# ELED03.net
KiCad netlist of a schematic drawn in EAGLE
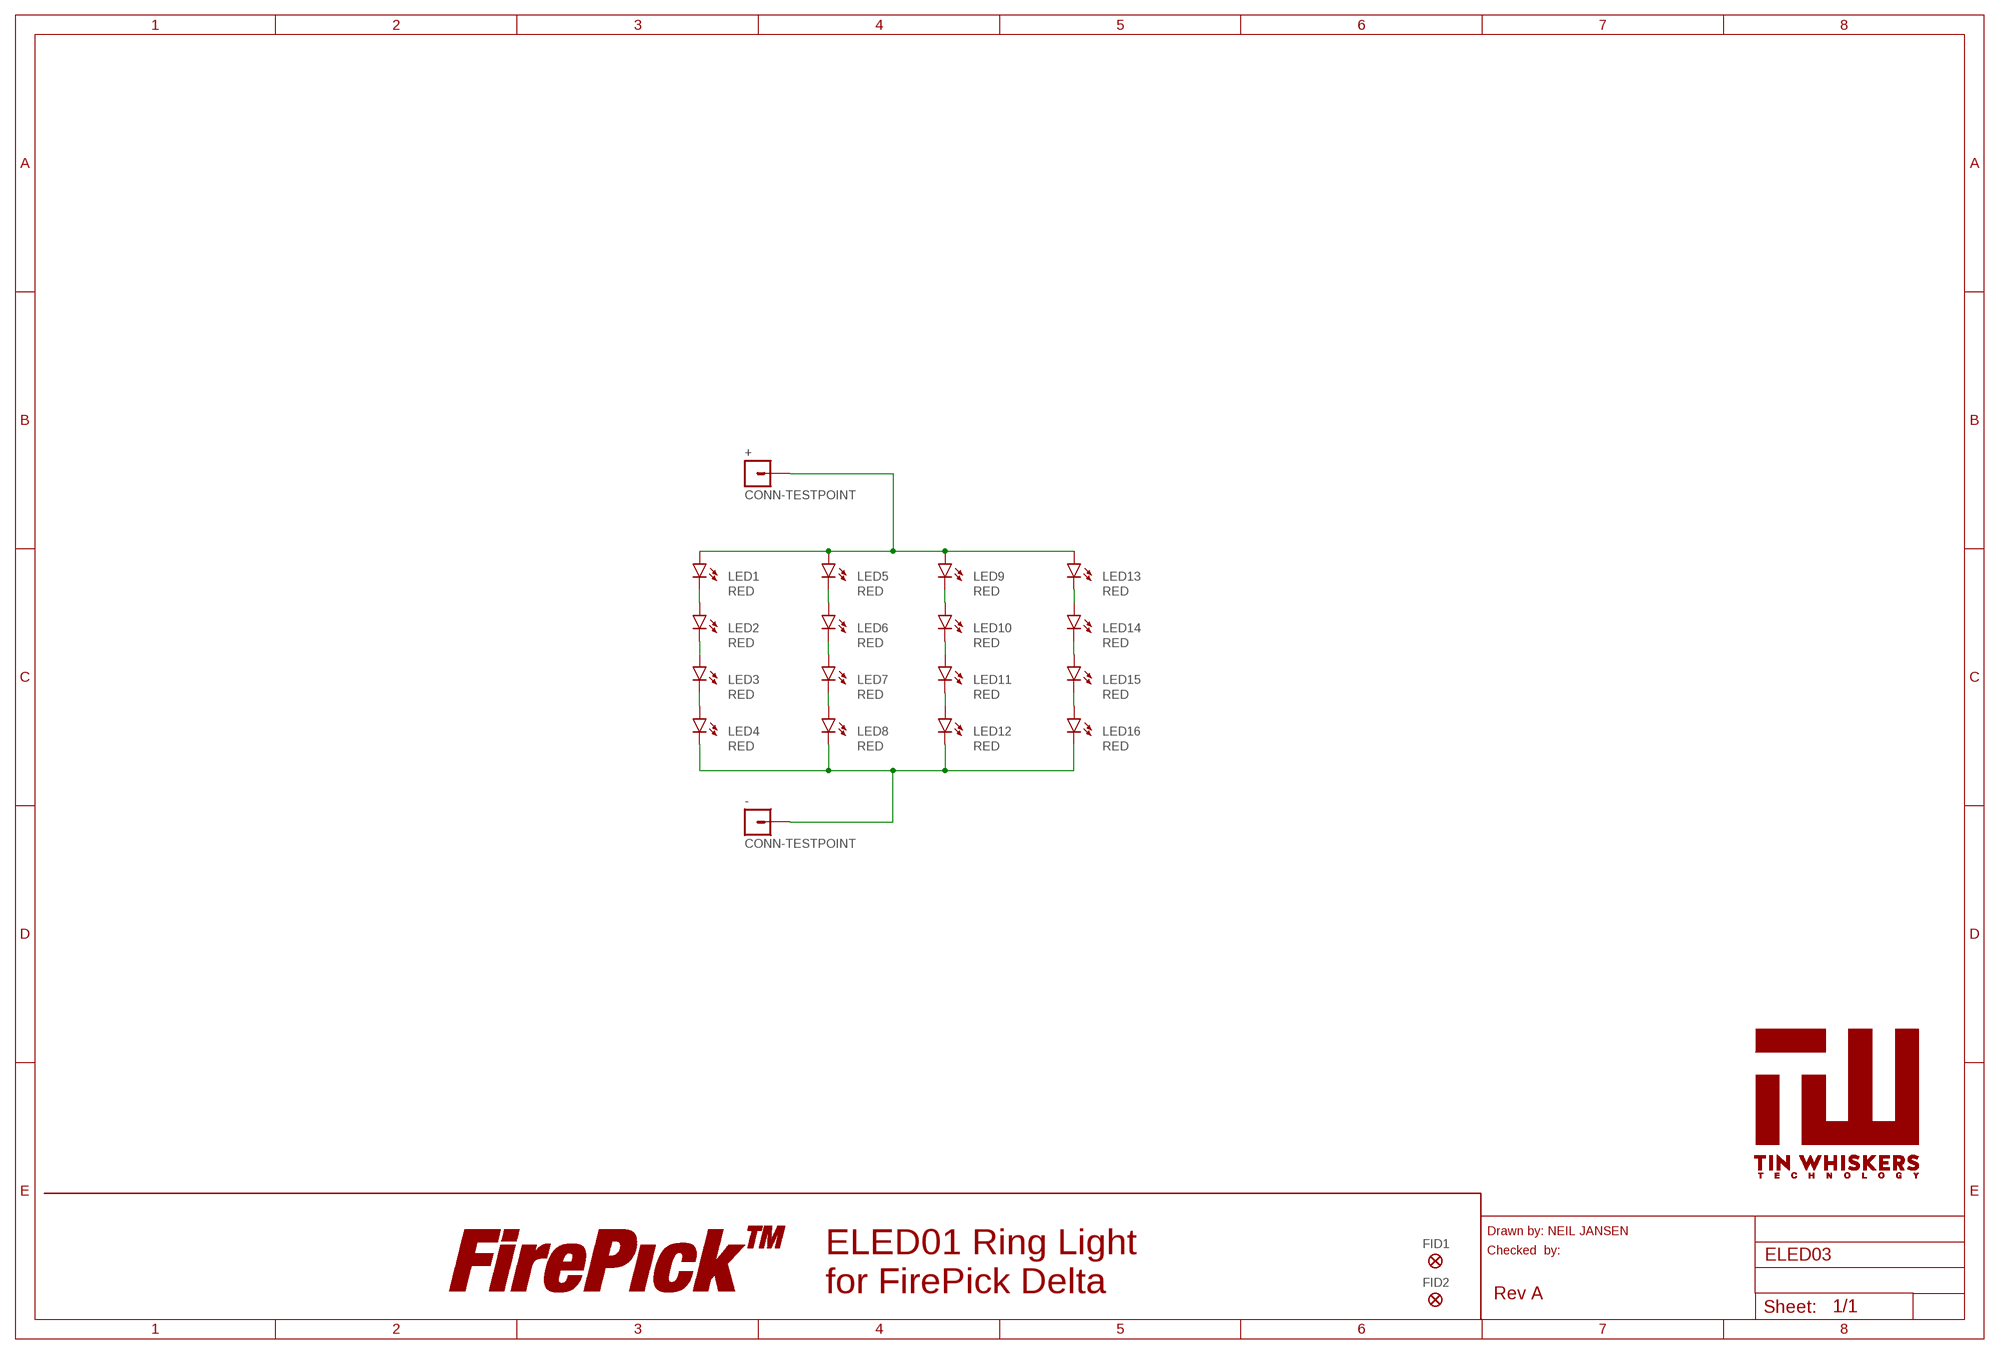
[diagram p0: schematic, sheet 1]

(export (version "E")
  (design (tool "Eeschema 10.0.6"))
  (components
    (comp (ref "+")
      (value "CONN-TESTPOINT")
      (footprint "eagle-import:CON-TESTPOINT")
      (libsource (lib "eagle-import") (part "CONN-TESTPOINT"))
    )
    (comp (ref "-")
      (value "CONN-TESTPOINT")
      (footprint "eagle-import:CON-TESTPOINT")
      (libsource (lib "eagle-import") (part "CONN-TESTPOINT"))
    )
    (comp (ref "FID1")
      (value "FIDUCIAL")
      (footprint "eagle-import:FIDUCIAL")
      (libsource (lib "eagle-import") (part "FIDUCIAL"))
    )
    (comp (ref "FID2")
      (value "FIDUCIAL")
      (footprint "eagle-import:FIDUCIAL")
      (libsource (lib "eagle-import") (part "FIDUCIAL"))
    )
    (comp (ref "LED1")
      (value "RED")
      (footprint "eagle-import:DIODE-1210")
      (fields (field (name "PARTNO") "QBLP650-IW"))
      (libsource (lib "eagle-import") (part "LED1210"))
    )
    (comp (ref "LED2")
      (value "RED")
      (footprint "eagle-import:DIODE-1210")
      (fields (field (name "PARTNO") "QBLP650-IW"))
      (libsource (lib "eagle-import") (part "LED1210"))
    )
    (comp (ref "LED3")
      (value "RED")
      (footprint "eagle-import:DIODE-1210")
      (fields (field (name "PARTNO") "QBLP650-IW"))
      (libsource (lib "eagle-import") (part "LED1210"))
    )
    (comp (ref "LED4")
      (value "RED")
      (footprint "eagle-import:DIODE-1210")
      (fields (field (name "PARTNO") "QBLP650-IW"))
      (libsource (lib "eagle-import") (part "LED1210"))
    )
    (comp (ref "LED5")
      (value "RED")
      (footprint "eagle-import:DIODE-1210")
      (fields (field (name "PARTNO") "QBLP650-IW"))
      (libsource (lib "eagle-import") (part "LED1210"))
    )
    (comp (ref "LED6")
      (value "RED")
      (footprint "eagle-import:DIODE-1210")
      (fields (field (name "PARTNO") "QBLP650-IW"))
      (libsource (lib "eagle-import") (part "LED1210"))
    )
    (comp (ref "LED7")
      (value "RED")
      (footprint "eagle-import:DIODE-1210")
      (fields (field (name "PARTNO") "QBLP650-IW"))
      (libsource (lib "eagle-import") (part "LED1210"))
    )
    (comp (ref "LED8")
      (value "RED")
      (footprint "eagle-import:DIODE-1210")
      (fields (field (name "PARTNO") "QBLP650-IW"))
      (libsource (lib "eagle-import") (part "LED1210"))
    )
    (comp (ref "LED9")
      (value "RED")
      (footprint "eagle-import:DIODE-1210")
      (fields (field (name "PARTNO") "QBLP650-IW"))
      (libsource (lib "eagle-import") (part "LED1210"))
    )
    (comp (ref "LED10")
      (value "RED")
      (footprint "eagle-import:DIODE-1210")
      (fields (field (name "PARTNO") "QBLP650-IW"))
      (libsource (lib "eagle-import") (part "LED1210"))
    )
    (comp (ref "LED11")
      (value "RED")
      (footprint "eagle-import:DIODE-1210")
      (fields (field (name "PARTNO") "QBLP650-IW"))
      (libsource (lib "eagle-import") (part "LED1210"))
    )
    (comp (ref "LED12")
      (value "RED")
      (footprint "eagle-import:DIODE-1210")
      (fields (field (name "PARTNO") "QBLP650-IW"))
      (libsource (lib "eagle-import") (part "LED1210"))
    )
    (comp (ref "LED13")
      (value "RED")
      (footprint "eagle-import:DIODE-1210")
      (fields (field (name "PARTNO") "QBLP650-IW"))
      (libsource (lib "eagle-import") (part "LED1210"))
    )
    (comp (ref "LED14")
      (value "RED")
      (footprint "eagle-import:DIODE-1210")
      (fields (field (name "PARTNO") "QBLP650-IW"))
      (libsource (lib "eagle-import") (part "LED1210"))
    )
    (comp (ref "LED15")
      (value "RED")
      (footprint "eagle-import:DIODE-1210")
      (fields (field (name "PARTNO") "QBLP650-IW"))
      (libsource (lib "eagle-import") (part "LED1210"))
    )
    (comp (ref "LED16")
      (value "RED")
      (footprint "eagle-import:DIODE-1210")
      (fields (field (name "PARTNO") "QBLP650-IW"))
      (libsource (lib "eagle-import") (part "LED1210"))
    )
    (comp (ref "LOGO4")
      (value "LOGO-FIREPICKMEDIUM")
      (footprint "eagle-import:LOGO-FIREPICK-MEDIUM")
      (libsource (lib "eagle-import") (part "LOGO-FIREPICKMEDIUM"))
    )
    (comp (ref "U$1")
      (value "TIN-WHISKERSSMALL")
      (footprint "eagle-import:TIN-WHISKERS-SMALL")
      (libsource (lib "eagle-import") (part "TIN-WHISKERSSMALL"))
    )
  )
  (nets
    (net (code "1") (name "Net-(+-2)") (class "Default")
      (node (ref "+") (pin "1") (pinfunction "2_1") (pintype "passive"))
      (node (ref "LED1") (pin "A") (pinfunction "A_A") (pintype "passive"))
      (node (ref "LED13") (pin "A") (pinfunction "A_A") (pintype "passive"))
      (node (ref "LED5") (pin "A") (pinfunction "A_A") (pintype "passive"))
      (node (ref "LED9") (pin "A") (pinfunction "A_A") (pintype "passive"))
    )
    (net (code "2") (name "Net-(--2)") (class "Default")
      (node (ref "-") (pin "1") (pinfunction "2_1") (pintype "passive"))
      (node (ref "LED12") (pin "K") (pinfunction "C_K") (pintype "passive"))
      (node (ref "LED16") (pin "K") (pinfunction "C_K") (pintype "passive"))
      (node (ref "LED4") (pin "K") (pinfunction "C_K") (pintype "passive"))
      (node (ref "LED8") (pin "K") (pinfunction "C_K") (pintype "passive"))
    )
    (net (code "3") (name "Net-(LED1-C)") (class "Default")
      (node (ref "LED1") (pin "K") (pinfunction "C_K") (pintype "passive"))
      (node (ref "LED2") (pin "A") (pinfunction "A_A") (pintype "passive"))
    )
    (net (code "4") (name "Net-(LED2-C)") (class "Default")
      (node (ref "LED2") (pin "K") (pinfunction "C_K") (pintype "passive"))
      (node (ref "LED3") (pin "A") (pinfunction "A_A") (pintype "passive"))
    )
    (net (code "5") (name "Net-(LED3-C)") (class "Default")
      (node (ref "LED3") (pin "K") (pinfunction "C_K") (pintype "passive"))
      (node (ref "LED4") (pin "A") (pinfunction "A_A") (pintype "passive"))
    )
    (net (code "6") (name "Net-(LED5-C)") (class "Default")
      (node (ref "LED5") (pin "K") (pinfunction "C_K") (pintype "passive"))
      (node (ref "LED6") (pin "A") (pinfunction "A_A") (pintype "passive"))
    )
    (net (code "7") (name "Net-(LED6-C)") (class "Default")
      (node (ref "LED6") (pin "K") (pinfunction "C_K") (pintype "passive"))
      (node (ref "LED7") (pin "A") (pinfunction "A_A") (pintype "passive"))
    )
    (net (code "8") (name "Net-(LED7-C)") (class "Default")
      (node (ref "LED7") (pin "K") (pinfunction "C_K") (pintype "passive"))
      (node (ref "LED8") (pin "A") (pinfunction "A_A") (pintype "passive"))
    )
    (net (code "9") (name "Net-(LED9-C)") (class "Default")
      (node (ref "LED10") (pin "A") (pinfunction "A_A") (pintype "passive"))
      (node (ref "LED9") (pin "K") (pinfunction "C_K") (pintype "passive"))
    )
    (net (code "10") (name "Net-(LED10-C)") (class "Default")
      (node (ref "LED10") (pin "K") (pinfunction "C_K") (pintype "passive"))
      (node (ref "LED11") (pin "A") (pinfunction "A_A") (pintype "passive"))
    )
    (net (code "11") (name "Net-(LED11-C)") (class "Default")
      (node (ref "LED11") (pin "K") (pinfunction "C_K") (pintype "passive"))
      (node (ref "LED12") (pin "A") (pinfunction "A_A") (pintype "passive"))
    )
    (net (code "12") (name "Net-(LED13-C)") (class "Default")
      (node (ref "LED13") (pin "K") (pinfunction "C_K") (pintype "passive"))
      (node (ref "LED14") (pin "A") (pinfunction "A_A") (pintype "passive"))
    )
    (net (code "13") (name "Net-(LED14-C)") (class "Default")
      (node (ref "LED14") (pin "K") (pinfunction "C_K") (pintype "passive"))
      (node (ref "LED15") (pin "A") (pinfunction "A_A") (pintype "passive"))
    )
    (net (code "14") (name "Net-(LED15-C)") (class "Default")
      (node (ref "LED15") (pin "K") (pinfunction "C_K") (pintype "passive"))
      (node (ref "LED16") (pin "A") (pinfunction "A_A") (pintype "passive"))
    )
  )
)
